# regulation.net
KiCad netlist of a schematic drawn in Altium Designer
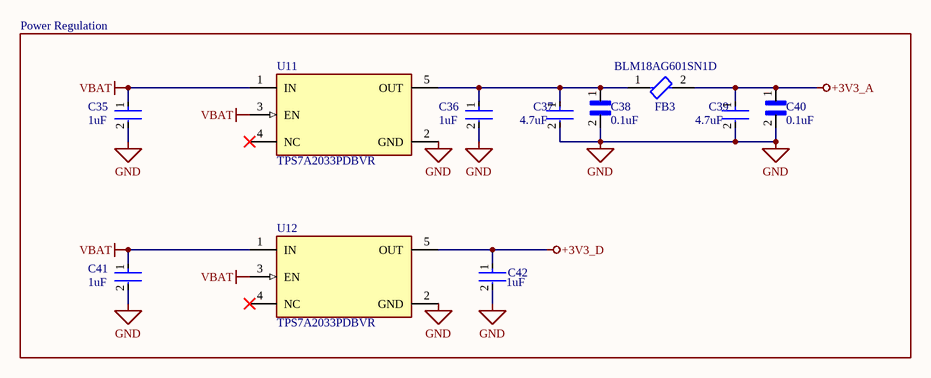
[diagram p0: regulation.SchDoc]

(export (version "E")
  (design (tool "Eeschema 10.0.6"))
  (components
    (comp (ref "C35")
      (value "1uF")
      (footprint "CC0805KKX7R7BB106")
      (description "16V 1uF X7R ±10% 0805 Multilayer Ceramic Capacitors MLCC - SMD/SMT ROHS")
      (fields
        (field (name "MANUFACTURER") "Yageo Group")
        (field (name "MANUFACTURER PART NUMBER") "CC0805KKX7R7BB105")
      )
      (libsource (lib "opm_lib") (part "CC0805KKX7R7BB105"))
    )
    (comp (ref "C36")
      (value "1uF")
      (footprint "CC0805KKX7R7BB106")
      (description "16V 1uF X7R ±10% 0805 Multilayer Ceramic Capacitors MLCC - SMD/SMT ROHS")
      (fields
        (field (name "MANUFACTURER") "Yageo Group")
        (field (name "MANUFACTURER PART NUMBER") "CC0805KKX7R7BB105")
      )
      (libsource (lib "opm_lib") (part "CC0805KKX7R7BB105"))
    )
    (comp (ref "C37")
      (value "4.7uF")
      (footprint "CC0805KKX7R7BB106")
      (description "16V 4.7uF X7R ±10% 0805 Multilayer Ceramic Capacitors MLCC - SMD/SMT ROHS")
      (fields
        (field (name "MANUFACTURER") "Yageo Group")
        (field (name "MANUFACTURER PART NUMBER") "CC0805KKX7R7BB475")
      )
      (libsource (lib "opm_lib") (part "CC0805KKX7R7BB475"))
    )
    (comp (ref "C38")
      (value "0.1uF")
      (footprint "CC0603JRX7R8BB104")
      (description "25V 100nF X7R ±5% 0603 Multilayer Ceramic Capacitors MLCC - SMD/SMT ROHS")
      (fields
        (field (name "MANUFACTURER") "Yageo Group")
        (field (name "MANUFACTURER PART NUMBER") "CC0603JRX7R8BB104")
      )
      (libsource (lib "opm_lib") (part "CC0603JRX7R8BB104"))
    )
    (comp (ref "C39")
      (value "4.7uF")
      (footprint "CC0805KKX7R7BB106")
      (description "16V 4.7uF X7R ±10% 0805 Multilayer Ceramic Capacitors MLCC - SMD/SMT ROHS")
      (fields
        (field (name "MANUFACTURER") "Yageo Group")
        (field (name "MANUFACTURER PART NUMBER") "CC0805KKX7R7BB475")
      )
      (libsource (lib "opm_lib") (part "CC0805KKX7R7BB475"))
    )
    (comp (ref "C40")
      (value "0.1uF")
      (footprint "CC0603JRX7R8BB104")
      (description "25V 100nF X7R ±5% 0603 Multilayer Ceramic Capacitors MLCC - SMD/SMT ROHS")
      (fields
        (field (name "MANUFACTURER") "Yageo Group")
        (field (name "MANUFACTURER PART NUMBER") "CC0603JRX7R8BB104")
      )
      (libsource (lib "opm_lib") (part "CC0603JRX7R8BB104"))
    )
    (comp (ref "C41")
      (value "1uF")
      (footprint "CC0805KKX7R7BB106")
      (description "16V 1uF X7R ±10% 0805 Multilayer Ceramic Capacitors MLCC - SMD/SMT ROHS")
      (fields
        (field (name "MANUFACTURER") "Yageo Group")
        (field (name "MANUFACTURER PART NUMBER") "CC0805KKX7R7BB105")
      )
      (libsource (lib "opm_lib") (part "CC0805KKX7R7BB105"))
    )
    (comp (ref "C42")
      (value "1uF")
      (footprint "CC0805KKX7R7BB106")
      (description "16V 1uF X7R ±10% 0805 Multilayer Ceramic Capacitors MLCC - SMD/SMT ROHS")
      (fields
        (field (name "MANUFACTURER") "Yageo Group")
        (field (name "MANUFACTURER PART NUMBER") "CC0805KKX7R7BB105")
      )
      (libsource (lib "opm_lib") (part "CC0805KKX7R7BB105"))
    )
    (comp (ref "FB3")
      (value "BLM18AG601SN1D")
      (footprint "BLM18AG601SN1D")
      (description "Ferrite Beads Multi-Layer 600Ohm 25% 100MHz 500mA 380mOhm DCR 0603 Automotive Paper T/R")
      (fields (field (name "MANUFACTURER") "Murata") (field (name "TOLERANCE") "25%"))
      (libsource (lib "opm_lib") (part "BLM18AG601SN1D"))
    )
    (comp (ref "U11")
      (value "TPS7A2033PDBVR")
      (footprint "TPS7A2033PDBVR")
      (description "300mA ultra-low-noise low-IQ low-dropout (LDO) linear regulator with high PSRR 5-SOT-23 -40 to 125")
      (fields (field (name "MANUFACTURER") "Texas Instruments"))
      (libsource (lib "opm_lib") (part "TPS7A2033PDBVR"))
    )
    (comp (ref "U12")
      (value "TPS7A2033PDBVR")
      (footprint "TPS7A2033PDBVR")
      (description "300mA ultra-low-noise low-IQ low-dropout (LDO) linear regulator with high PSRR 5-SOT-23 -40 to 125")
      (fields (field (name "MANUFACTURER") "Texas Instruments"))
      (libsource (lib "opm_lib") (part "TPS7A2033PDBVR"))
    )
  )
  (nets
    (net (code "1") (name "+3V3_A") (class "Default")
      (node (ref "C39") (pin "1") (pinfunction "1_1") (pintype "passive"))
      (node (ref "C40") (pin "1") (pinfunction "1_1") (pintype "passive"))
      (node (ref "FB3") (pin "2") (pinfunction "2_2") (pintype "passive"))
    )
    (net (code "2") (name "+3V3_D") (class "Default")
      (node (ref "C42") (pin "1") (pinfunction "1_1") (pintype "passive"))
      (node (ref "U12") (pin "5") (pinfunction "OUT_5") (pintype "passive"))
    )
    (net (code "3") (name "GND") (class "Default")
      (node (ref "C35") (pin "2") (pinfunction "2_2") (pintype "passive"))
      (node (ref "C36") (pin "2") (pinfunction "2_2") (pintype "passive"))
      (node (ref "C37") (pin "2") (pinfunction "2_2") (pintype "passive"))
      (node (ref "C38") (pin "2") (pinfunction "2_2") (pintype "passive"))
      (node (ref "C39") (pin "2") (pinfunction "2_2") (pintype "passive"))
      (node (ref "C40") (pin "2") (pinfunction "2_2") (pintype "passive"))
      (node (ref "C41") (pin "2") (pinfunction "2_2") (pintype "passive"))
      (node (ref "C42") (pin "2") (pinfunction "2_2") (pintype "passive"))
      (node (ref "U11") (pin "2") (pinfunction "GND_2") (pintype "power_in"))
      (node (ref "U12") (pin "2") (pinfunction "GND_2") (pintype "power_in"))
    )
    (net (code "4") (name "Net-(U11-OUT)") (class "Default")
      (node (ref "C36") (pin "1") (pinfunction "1_1") (pintype "passive"))
      (node (ref "C37") (pin "1") (pinfunction "1_1") (pintype "passive"))
      (node (ref "C38") (pin "1") (pinfunction "1_1") (pintype "passive"))
      (node (ref "FB3") (pin "1") (pinfunction "1_1") (pintype "passive"))
      (node (ref "U11") (pin "5") (pinfunction "OUT_5") (pintype "passive"))
    )
    (net (code "5") (name "VBAT") (class "Default")
      (node (ref "C35") (pin "1") (pinfunction "1_1") (pintype "passive"))
      (node (ref "C41") (pin "1") (pinfunction "1_1") (pintype "passive"))
      (node (ref "U11") (pin "1") (pinfunction "IN_1") (pintype "power_in"))
      (node (ref "U11") (pin "3") (pinfunction "EN_3") (pintype "input"))
      (node (ref "U12") (pin "1") (pinfunction "IN_1") (pintype "power_in"))
      (node (ref "U12") (pin "3") (pinfunction "EN_3") (pintype "input"))
    )
    (net (code "6") (name "unconnected-(U11-NC-Pad4)") (class "Default")
      (node (ref "U11") (pin "4") (pinfunction "NC_4") (pintype "passive+no_connect"))
    )
    (net (code "7") (name "unconnected-(U12-NC-Pad4)") (class "Default")
      (node (ref "U12") (pin "4") (pinfunction "NC_4") (pintype "passive+no_connect"))
    )
  )
)
